# 05_LMS7002M_RF1.net
KiCad netlist of a schematic drawn in Altium Designer
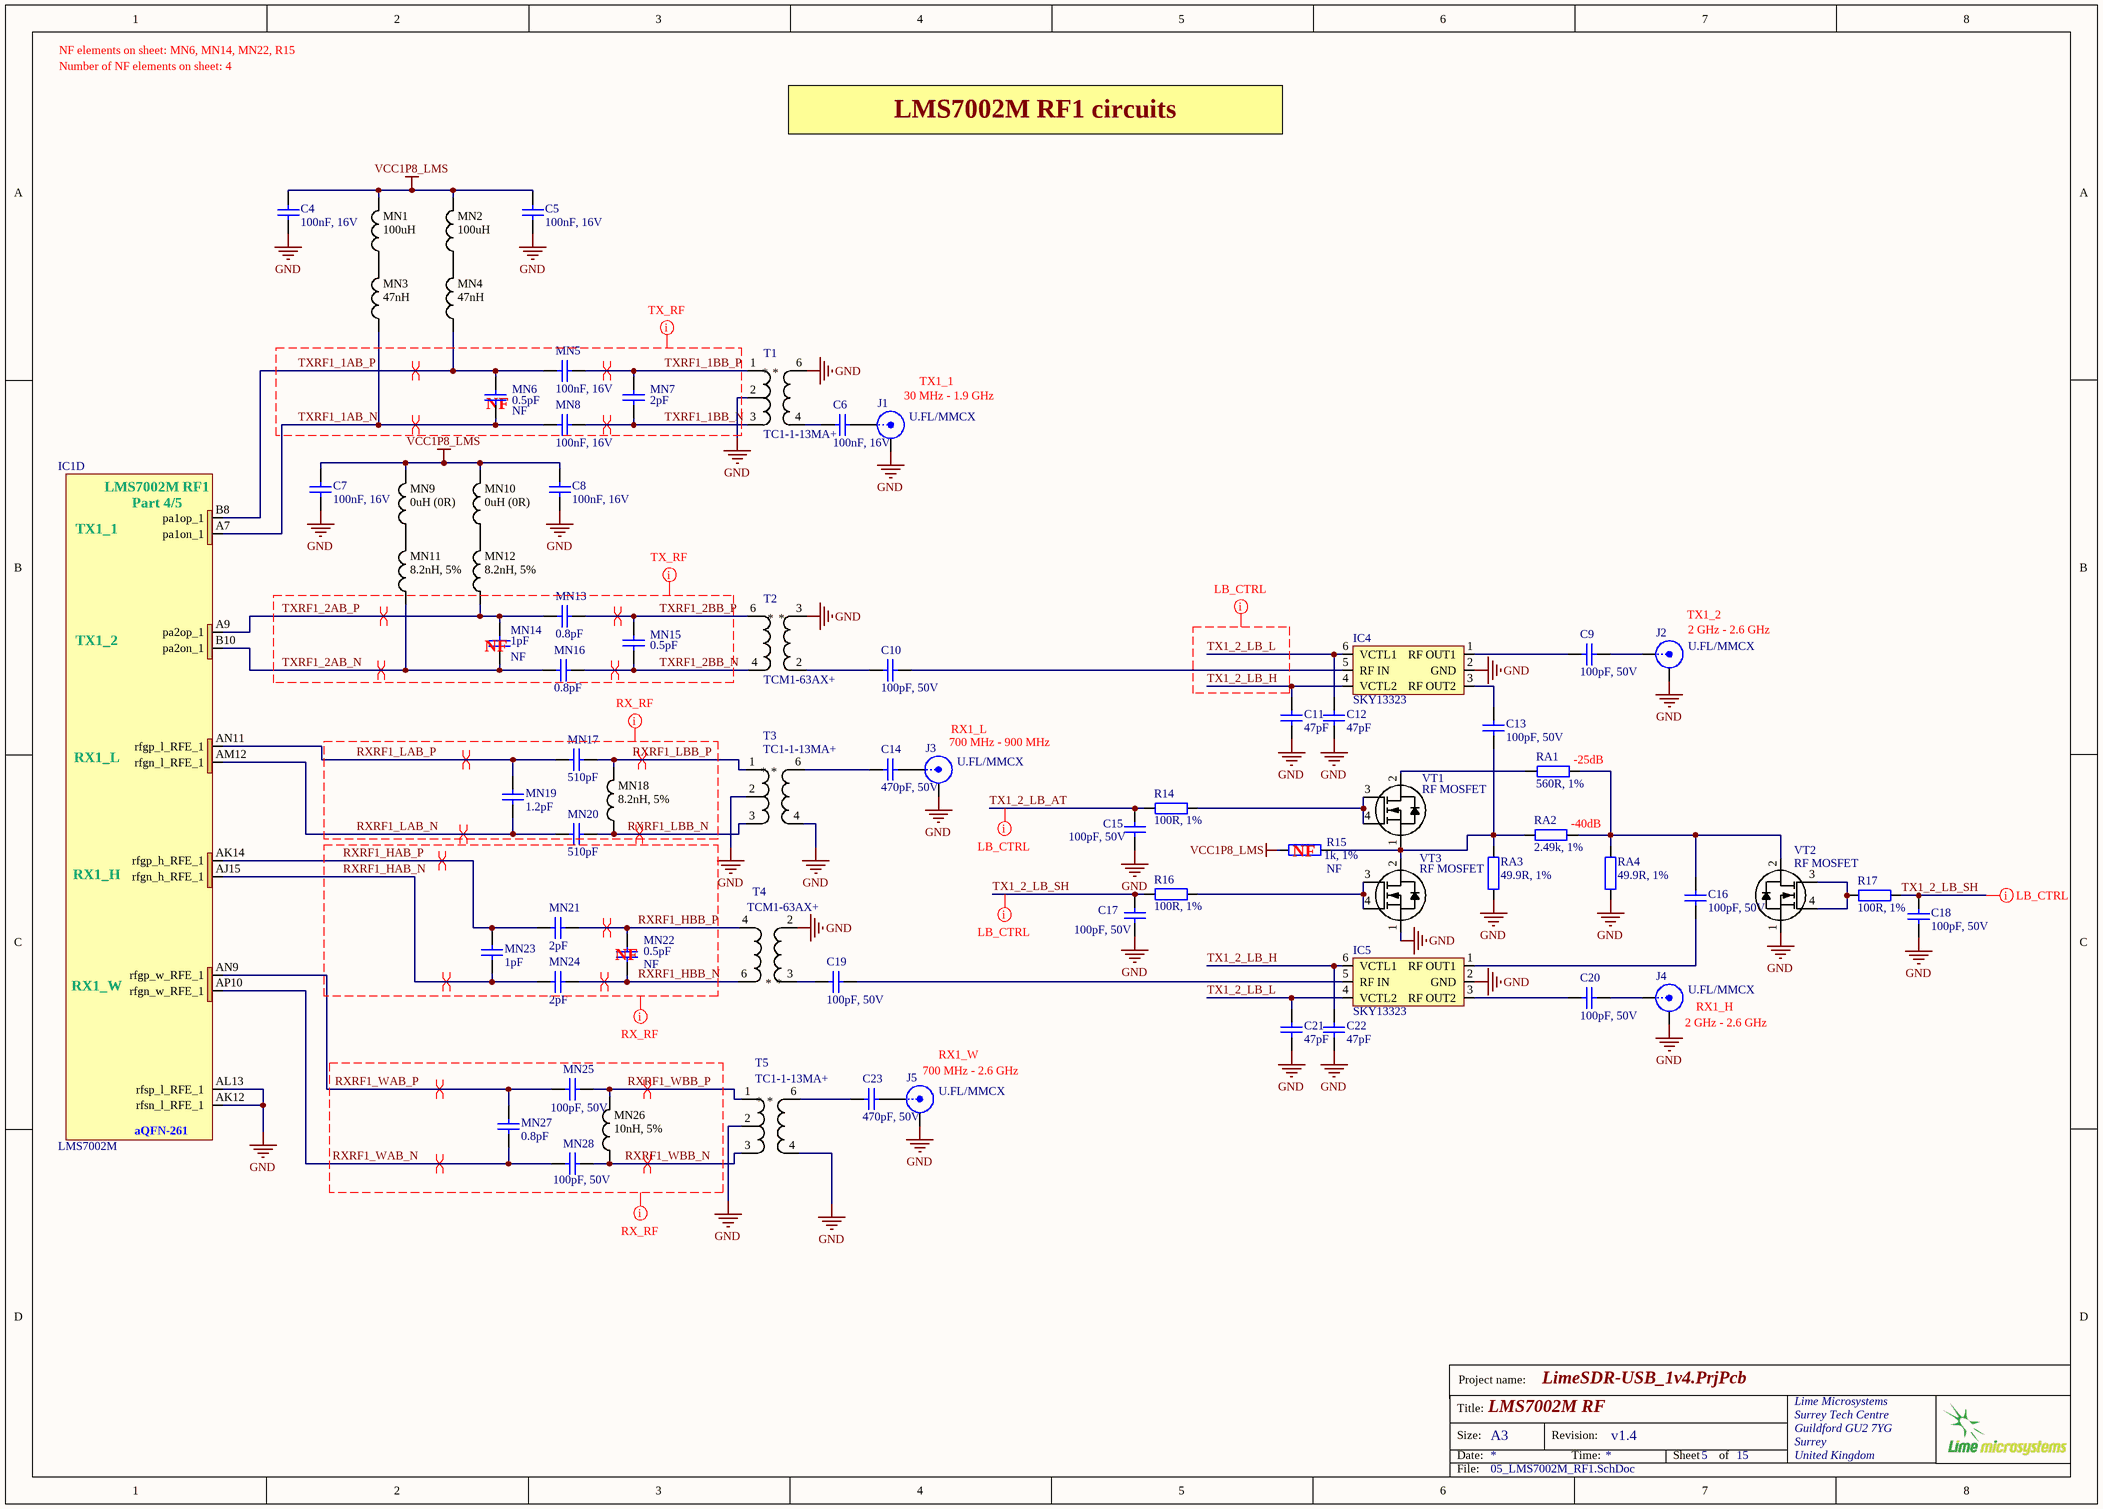
[diagram p0: 05_LMS7002M_RF1.SchDoc]

(export (version "E")
  (design (tool "Eeschema 10.0.6"))
  (components
    (comp (ref "C4")
      (value "100nF, 16V")
      (footprint "CAP0402")
      (fields
        (field (name "MANUFACTURER") "Murata Electronics")
        (field (name "TOLERANCE") "10 %")
        (field (name "MANUFACTURER PART NUMBER") "GRM155R71C104KA88D")
      )
      (libsource (lib "LimeMicroAltiumLib_schLib") (part "Cap_0402"))
    )
    (comp (ref "C5")
      (value "100nF, 16V")
      (footprint "CAP0402")
      (fields
        (field (name "MANUFACTURER") "Murata Electronics")
        (field (name "TOLERANCE") "10 %")
        (field (name "MANUFACTURER PART NUMBER") "GRM155R71C104KA88D")
      )
      (libsource (lib "LimeMicroAltiumLib_schLib") (part "Cap_0402"))
    )
    (comp (ref "C6")
      (value "100nF, 16V")
      (footprint "CAP0402")
      (fields
        (field (name "MANUFACTURER") "Murata Electronics")
        (field (name "TOLERANCE") "10 %")
        (field (name "MANUFACTURER PART NUMBER") "GRM155R71C104KA88D")
      )
      (libsource (lib "LimeMicroAltiumLib_schLib") (part "Cap_0402"))
    )
    (comp (ref "C7")
      (value "100nF, 16V")
      (footprint "CAP0402")
      (fields
        (field (name "MANUFACTURER") "Murata Electronics")
        (field (name "TOLERANCE") "10 %")
        (field (name "MANUFACTURER PART NUMBER") "GRM155R71C104KA88D")
      )
      (libsource (lib "LimeMicroAltiumLib_schLib") (part "Cap_0402"))
    )
    (comp (ref "C8")
      (value "100nF, 16V")
      (footprint "CAP0402")
      (fields
        (field (name "MANUFACTURER") "Murata Electronics")
        (field (name "TOLERANCE") "10 %")
        (field (name "MANUFACTURER PART NUMBER") "GRM155R71C104KA88D")
      )
      (libsource (lib "LimeMicroAltiumLib_schLib") (part "Cap_0402"))
    )
    (comp (ref "C9")
      (value "100pF, 50V")
      (footprint "CAP0402")
      (fields (field (name "TOLERANCE") "±5%") (field (name "MANUFACTURER") "Yageo"))
      (libsource (lib "LimeMicroAltiumLib_schLib") (part "Cap_0402"))
    )
    (comp (ref "C10")
      (value "100pF, 50V")
      (footprint "CAP0402")
      (fields (field (name "TOLERANCE") "±5%") (field (name "MANUFACTURER") "Yageo"))
      (libsource (lib "LimeMicroAltiumLib_schLib") (part "Cap_0402"))
    )
    (comp (ref "C11")
      (value "47pF")
      (footprint "CAP0402")
      (fields (field (name "TOLERANCE") "±1%") (field (name "MANUFACTURER") "TDK Corporation"))
      (libsource (lib "LimeMicroAltiumLib_schLib") (part "Cap_0402"))
    )
    (comp (ref "C12")
      (value "47pF")
      (footprint "CAP0402")
      (fields (field (name "TOLERANCE") "±1%") (field (name "MANUFACTURER") "TDK Corporation"))
      (libsource (lib "LimeMicroAltiumLib_schLib") (part "Cap_0402"))
    )
    (comp (ref "C13")
      (value "100pF, 50V")
      (footprint "CAP0402")
      (fields (field (name "TOLERANCE") "±5%") (field (name "MANUFACTURER") "Yageo"))
      (libsource (lib "LimeMicroAltiumLib_schLib") (part "Cap_0402"))
    )
    (comp (ref "C14")
      (value "470pF, 50V")
      (footprint "CAP0402")
      (fields
        (field (name "MANUFACTURER PART NUMBER") "C1005C0G1H471J050BA")
        (field (name "TOLERANCE") "±5%")
        (field (name "MANUFACTURER") "TDK Corporation")
      )
      (libsource (lib "LimeMicroAltiumLib_schLib") (part "Cap_0402"))
    )
    (comp (ref "C15")
      (value "100pF, 50V")
      (footprint "CAP0402")
      (fields (field (name "TOLERANCE") "±5%") (field (name "MANUFACTURER") "Yageo"))
      (libsource (lib "LimeMicroAltiumLib_schLib") (part "Cap_0402"))
    )
    (comp (ref "C16")
      (value "100pF, 50V")
      (footprint "CAP0402")
      (fields (field (name "TOLERANCE") "±5%") (field (name "MANUFACTURER") "Yageo"))
      (libsource (lib "LimeMicroAltiumLib_schLib") (part "Cap_0402"))
    )
    (comp (ref "C17")
      (value "100pF, 50V")
      (footprint "CAP0402")
      (fields (field (name "TOLERANCE") "±5%") (field (name "MANUFACTURER") "Yageo"))
      (libsource (lib "LimeMicroAltiumLib_schLib") (part "Cap_0402"))
    )
    (comp (ref "C18")
      (value "100pF, 50V")
      (footprint "CAP0402")
      (fields (field (name "TOLERANCE") "±5%") (field (name "MANUFACTURER") "Yageo"))
      (libsource (lib "LimeMicroAltiumLib_schLib") (part "Cap_0402"))
    )
    (comp (ref "C19")
      (value "100pF, 50V")
      (footprint "CAP0402")
      (fields (field (name "TOLERANCE") "±5%") (field (name "MANUFACTURER") "Yageo"))
      (libsource (lib "LimeMicroAltiumLib_schLib") (part "Cap_0402"))
    )
    (comp (ref "C20")
      (value "100pF, 50V")
      (footprint "CAP0402")
      (fields (field (name "TOLERANCE") "±5%") (field (name "MANUFACTURER") "Yageo"))
      (libsource (lib "LimeMicroAltiumLib_schLib") (part "Cap_0402"))
    )
    (comp (ref "C21")
      (value "47pF")
      (footprint "CAP0402")
      (fields (field (name "TOLERANCE") "±1%") (field (name "MANUFACTURER") "TDK Corporation"))
      (libsource (lib "LimeMicroAltiumLib_schLib") (part "Cap_0402"))
    )
    (comp (ref "C22")
      (value "47pF")
      (footprint "CAP0402")
      (fields (field (name "TOLERANCE") "±1%") (field (name "MANUFACTURER") "TDK Corporation"))
      (libsource (lib "LimeMicroAltiumLib_schLib") (part "Cap_0402"))
    )
    (comp (ref "C23")
      (value "470pF, 50V")
      (footprint "CAP0402")
      (fields
        (field (name "MANUFACTURER PART NUMBER") "C1005C0G1H471J050BA")
        (field (name "TOLERANCE") "±5%")
        (field (name "MANUFACTURER") "TDK Corporation")
      )
      (libsource (lib "LimeMicroAltiumLib_schLib") (part "Cap_0402"))
    )
    (comp (ref "IC1")
      (value "LMS7002M")
      (footprint "LMS7002M_v3")
      (fields (field (name "MANUFACTURER") "Lime Microsystems"))
      (libsource (lib "LimeMicroAltiumLib_schLib") (part "LMS7002M"))
    )
    (comp (ref "IC4")
      (value "SKY13323")
      (footprint "SKY13323-378LF")
      (description "SKY13323-378LF: 0.1-3.0 GHz GaAs SPDT Switch")
      (fields (field (name "MANUFACTURER") "Skyworks Solutions Inc."))
      (libsource (lib "LimeMicroAltiumLib_schLib") (part "SKY13323"))
    )
    (comp (ref "IC5")
      (value "SKY13323")
      (footprint "SKY13323-378LF")
      (description "SKY13323-378LF: 0.1-3.0 GHz GaAs SPDT Switch")
      (fields (field (name "MANUFACTURER") "Skyworks Solutions Inc."))
      (libsource (lib "LimeMicroAltiumLib_schLib") (part "SKY13323"))
    )
    (comp (ref "J1")
      (value "U.FL/MMCX")
      (footprint "MMCX_UFL_conn_u")
      (description "CONN UMC RCPT STR 50 OHM SMD")
      (fields (field (name "MANUFACTURER") "Molex, LLC"))
      (libsource (lib "LimeMicroAltiumLib_schLib") (part "RF_IF_connector"))
    )
    (comp (ref "J2")
      (value "U.FL/MMCX")
      (footprint "MMCX_UFL_conn_u")
      (description "CONN UMC RCPT STR 50 OHM SMD")
      (fields (field (name "MANUFACTURER") "Molex, LLC"))
      (libsource (lib "LimeMicroAltiumLib_schLib") (part "RF_IF_connector"))
    )
    (comp (ref "J3")
      (value "U.FL/MMCX")
      (footprint "MMCX_UFL_conn_u")
      (description "CONN UMC RCPT STR 50 OHM SMD")
      (fields (field (name "MANUFACTURER") "Molex, LLC"))
      (libsource (lib "LimeMicroAltiumLib_schLib") (part "RF_IF_connector"))
    )
    (comp (ref "J4")
      (value "U.FL/MMCX")
      (footprint "MMCX_UFL_conn_u")
      (description "CONN UMC RCPT STR 50 OHM SMD")
      (fields (field (name "MANUFACTURER") "Molex, LLC"))
      (libsource (lib "LimeMicroAltiumLib_schLib") (part "RF_IF_connector"))
    )
    (comp (ref "J5")
      (value "U.FL/MMCX")
      (footprint "MMCX_UFL_conn_u")
      (description "CONN UMC RCPT STR 50 OHM SMD")
      (fields (field (name "MANUFACTURER") "Molex, LLC"))
      (libsource (lib "LimeMicroAltiumLib_schLib") (part "RF_IF_connector"))
    )
    (comp (ref "MN1")
      (value "100uH")
      (footprint "RES0805")
      (fields
        (field (name "TOLERANCE") "±10%")
        (field (name "MANUFACTURER") "TDK Corporation")
        (field (name "MANUFACTURER PART NUMBER") "MLF2012C101KT000")
      )
      (libsource (lib "LimeMicroAltiumLib_schLib") (part "Inductor_0603"))
    )
    (comp (ref "MN2")
      (value "100uH")
      (footprint "RES0805")
      (fields
        (field (name "TOLERANCE") "±10%")
        (field (name "MANUFACTURER") "TDK Corporation")
        (field (name "MANUFACTURER PART NUMBER") "MLF2012C101KT000")
      )
      (libsource (lib "LimeMicroAltiumLib_schLib") (part "Inductor_0603"))
    )
    (comp (ref "MN3")
      (value "47nH")
      (footprint "RES0402")
      (fields
        (field (name "MANUFACTURER") "COILCRAFT")
        (field (name "MANUFACTURER PART NUMBER") "0402HP-47NXJLU")
      )
      (libsource (lib "LimeMicroAltiumLib_schLib") (part "Inductor_0603"))
    )
    (comp (ref "MN4")
      (value "47nH")
      (footprint "RES0402")
      (fields
        (field (name "MANUFACTURER") "COILCRAFT")
        (field (name "MANUFACTURER PART NUMBER") "0402HP-47NXJLU")
      )
      (libsource (lib "LimeMicroAltiumLib_schLib") (part "Inductor_0603"))
    )
    (comp (ref "MN5")
      (value "100nF, 16V")
      (footprint "CAP0402")
      (fields
        (field (name "MANUFACTURER") "Murata Electronics")
        (field (name "TOLERANCE") "10 %")
        (field (name "MANUFACTURER PART NUMBER") "GRM155R71C104KA88D")
      )
      (libsource (lib "LimeMicroAltiumLib_schLib") (part "Cap_0402"))
    )
    (comp (ref "MN6")
      (value "0.5pF")
      (footprint "CAP0402")
      (fields
        (field (name "ASSEMBLY INFO") "NF")
        (field (name "TOLERANCE") "±0.25pF")
        (field (name "MANUFACTURER") "Yageo")
      )
      (libsource (lib "LimeMicroAltiumLib_schLib") (part "Cap_0402"))
    )
    (comp (ref "MN7")
      (value "2pF")
      (footprint "CAP0402")
      (fields (field (name "MANUFACTURER PART NUMBER") "04025U2R0BAT2A") (field (name "MANUFACTURER") "AVX"))
      (libsource (lib "LimeMicroAltiumLib_schLib") (part "Cap_0402"))
    )
    (comp (ref "MN8")
      (value "100nF, 16V")
      (footprint "CAP0402")
      (fields
        (field (name "MANUFACTURER") "Murata Electronics")
        (field (name "TOLERANCE") "10 %")
        (field (name "MANUFACTURER PART NUMBER") "GRM155R71C104KA88D")
      )
      (libsource (lib "LimeMicroAltiumLib_schLib") (part "Cap_0402"))
    )
    (comp (ref "MN9")
      (value "0uH (0R)")
      (footprint "RES0805")
      (fields (field (name "MANUFACTURER") "BOURNS"))
      (libsource (lib "LimeMicroAltiumLib_schLib") (part "Inductor_0603"))
    )
    (comp (ref "MN10")
      (value "0uH (0R)")
      (footprint "RES0805")
      (fields (field (name "MANUFACTURER") "BOURNS"))
      (libsource (lib "LimeMicroAltiumLib_schLib") (part "Inductor_0603"))
    )
    (comp (ref "MN11")
      (value "8.2nH, 5%")
      (footprint "RES0402")
      (fields (field (name "MANUFACTURER") "COILCRAFT"))
      (libsource (lib "LimeMicroAltiumLib_schLib") (part "Inductor_0603"))
    )
    (comp (ref "MN12")
      (value "8.2nH, 5%")
      (footprint "RES0402")
      (fields (field (name "MANUFACTURER") "COILCRAFT"))
      (libsource (lib "LimeMicroAltiumLib_schLib") (part "Inductor_0603"))
    )
    (comp (ref "MN13")
      (value "0.8pF")
      (footprint "CAP0402")
      (fields
        (field (name "TOLERANCE") "±0.1pF")
        (field (name "MANUFACTURER") "Murata Electronics North America")
        (field (name "MANUFACTURER PART NUMBER") "GRM1555C1HR80BA01D")
      )
      (libsource (lib "LimeMicroAltiumLib_schLib") (part "Cap_0402"))
    )
    (comp (ref "MN14")
      (value "1pF")
      (footprint "CAP0402")
      (fields
        (field (name "ASSEMBLY INFO") "NF")
        (field (name "MANUFACTURER") "TDK Corporation")
        (field (name "TOLERANCE") "±0.1pF")
      )
      (libsource (lib "LimeMicroAltiumLib_schLib") (part "Cap_0402"))
    )
    (comp (ref "MN15")
      (value "0.5pF")
      (footprint "CAP0402")
      (fields (field (name "TOLERANCE") "±0.25pF") (field (name "MANUFACTURER") "Yageo"))
      (libsource (lib "LimeMicroAltiumLib_schLib") (part "Cap_0402"))
    )
    (comp (ref "MN16")
      (value "0.8pF")
      (footprint "CAP0402")
      (fields
        (field (name "TOLERANCE") "±0.1pF")
        (field (name "MANUFACTURER") "Murata Electronics North America")
        (field (name "MANUFACTURER PART NUMBER") "GRM1555C1HR80BA01D")
      )
      (libsource (lib "LimeMicroAltiumLib_schLib") (part "Cap_0402"))
    )
    (comp (ref "MN17")
      (value "510pF")
      (footprint "CAP0402")
      (fields
        (field (name "TOLERANCE") "±5%")
        (field (name "MANUFACTURER") "Murata Electronics North America")
        (field (name "MANUFACTURER PART NUMBER") "GRM1555C1H511JA01D")
      )
      (libsource (lib "LimeMicroAltiumLib_schLib") (part "Cap_0402"))
    )
    (comp (ref "MN18")
      (value "8.2nH, 5%")
      (footprint "RES0402")
      (fields (field (name "MANUFACTURER") "COILCRAFT"))
      (libsource (lib "LimeMicroAltiumLib_schLib") (part "Inductor_0603"))
    )
    (comp (ref "MN19")
      (value "1.2pF")
      (footprint "CAP0402")
      (fields
        (field (name "MANUFACTURER") "Murata Electronics North America")
        (field (name "MANUFACTURER PART NUMBER") "GRM1555C1H1R2CA01D")
        (field (name "TOLERANCE") "±0.25pF")
      )
      (libsource (lib "LimeMicroAltiumLib_schLib") (part "Cap_0402"))
    )
    (comp (ref "MN20")
      (value "510pF")
      (footprint "CAP0402")
      (fields
        (field (name "TOLERANCE") "±5%")
        (field (name "MANUFACTURER") "Murata Electronics North America")
        (field (name "MANUFACTURER PART NUMBER") "GRM1555C1H511JA01D")
      )
      (libsource (lib "LimeMicroAltiumLib_schLib") (part "Cap_0402"))
    )
    (comp (ref "MN21")
      (value "2pF")
      (footprint "CAP0402")
      (fields (field (name "MANUFACTURER PART NUMBER") "04025U2R0BAT2A") (field (name "MANUFACTURER") "AVX"))
      (libsource (lib "LimeMicroAltiumLib_schLib") (part "Cap_0402"))
    )
    (comp (ref "MN22")
      (value "0.5pF")
      (footprint "CAP0402")
      (fields
        (field (name "ASSEMBLY INFO") "NF")
        (field (name "TOLERANCE") "±0.25pF")
        (field (name "MANUFACTURER") "Yageo")
      )
      (libsource (lib "LimeMicroAltiumLib_schLib") (part "Cap_0402"))
    )
    (comp (ref "MN23")
      (value "1pF")
      (footprint "CAP0402")
      (fields (field (name "MANUFACTURER") "TDK Corporation") (field (name "TOLERANCE") "±0.1pF"))
      (libsource (lib "LimeMicroAltiumLib_schLib") (part "Cap_0402"))
    )
    (comp (ref "MN24")
      (value "2pF")
      (footprint "CAP0402")
      (fields (field (name "MANUFACTURER PART NUMBER") "04025U2R0BAT2A") (field (name "MANUFACTURER") "AVX"))
      (libsource (lib "LimeMicroAltiumLib_schLib") (part "Cap_0402"))
    )
    (comp (ref "MN25")
      (value "100pF, 50V")
      (footprint "CAP0402")
      (fields (field (name "TOLERANCE") "±5%") (field (name "MANUFACTURER") "Yageo"))
      (libsource (lib "LimeMicroAltiumLib_schLib") (part "Cap_0402"))
    )
    (comp (ref "MN26")
      (value "10nH, 5%")
      (footprint "RES0402")
      (fields (field (name "MANUFACTURER") "COILCRAFT"))
      (libsource (lib "LimeMicroAltiumLib_schLib") (part "Inductor_0603"))
    )
    (comp (ref "MN27")
      (value "0.8pF")
      (footprint "CAP0402")
      (fields
        (field (name "TOLERANCE") "±0.1pF")
        (field (name "MANUFACTURER") "Murata Electronics North America")
        (field (name "MANUFACTURER PART NUMBER") "GRM1555C1HR80BA01D")
      )
      (libsource (lib "LimeMicroAltiumLib_schLib") (part "Cap_0402"))
    )
    (comp (ref "MN28")
      (value "100pF, 50V")
      (footprint "CAP0402")
      (fields (field (name "TOLERANCE") "±5%") (field (name "MANUFACTURER") "Yageo"))
      (libsource (lib "LimeMicroAltiumLib_schLib") (part "Cap_0402"))
    )
    (comp (ref "R14")
      (value "100R, 1%")
      (footprint "RES0402")
      (fields (field (name "TOLERANCE") "±1%") (field (name "MANUFACTURER") "Stackpole Electronics Inc."))
      (libsource (lib "LimeFPGAboard_schLib") (part "Res_0402"))
    )
    (comp (ref "R15")
      (value "1k, 1%")
      (footprint "RES0402")
      (fields
        (field (name "ASSEMBLY INFO") "NF")
        (field (name "MANUFACTURER") "Stackpole Electronics Inc")
        (field (name "TOLERANCE") "±1%")
      )
      (libsource (lib "LimeMicroAltiumLib_schLib") (part "Res_0402"))
    )
    (comp (ref "R16")
      (value "100R, 1%")
      (footprint "RES0402")
      (fields (field (name "TOLERANCE") "±1%") (field (name "MANUFACTURER") "Stackpole Electronics Inc."))
      (libsource (lib "LimeFPGAboard_schLib") (part "Res_0402"))
    )
    (comp (ref "R17")
      (value "100R, 1%")
      (footprint "RES0402")
      (fields (field (name "TOLERANCE") "±1%") (field (name "MANUFACTURER") "Stackpole Electronics Inc."))
      (libsource (lib "LimeFPGAboard_schLib") (part "Res_0402"))
    )
    (comp (ref "RA1")
      (value "560R, 1%")
      (footprint "RES0402")
      (fields
        (field (name "MANUFACTURER PART NUMBER") "CRCW0402560RFKED")
        (field (name "TOLERANCE") "±1%")
        (field (name "MANUFACTURER") "Vishay Dale")
      )
      (libsource (lib "LimeMicroAltiumLib_schLib") (part "Res_0402"))
    )
    (comp (ref "RA2")
      (value "2.49k, 1%")
      (footprint "RES0402")
      (fields
        (field (name "TOLERANCE") "±1%")
        (field (name "MANUFACTURER PART NUMBER") "RC0402FR-072K49L")
        (field (name "MANUFACTURER") "Yageo")
      )
      (libsource (lib "LimeMicroAltiumLib_schLib") (part "Res_0402"))
    )
    (comp (ref "RA3")
      (value "49.9R, 1%")
      (footprint "RES0402")
      (fields
        (field (name "TOLERANCE") "±1%")
        (field (name "MANUFACTURER") "Samsung Electro-Mechanics America, Inc.")
        (field (name "MANUFACTURER PART NUMBER") "RC1005F49R9CS")
      )
      (libsource (lib "LimeMicroAltiumLib_schLib") (part "Res_0402"))
    )
    (comp (ref "RA4")
      (value "49.9R, 1%")
      (footprint "RES0402")
      (fields
        (field (name "TOLERANCE") "±1%")
        (field (name "MANUFACTURER") "Samsung Electro-Mechanics America, Inc.")
        (field (name "MANUFACTURER PART NUMBER") "RC1005F49R9CS")
      )
      (libsource (lib "LimeMicroAltiumLib_schLib") (part "Res_0402"))
    )
    (comp (ref "T1")
      (value "TC1-1-13MA+")
      (footprint "TC1-1-13MA+_v2")
      (fields (field (name "MANUFACTURER") "Mini-Circuits"))
      (libsource (lib "LimeMicroAltiumLib_schLib") (part "Balun"))
    )
    (comp (ref "T2")
      (value "TCM1-63AX+")
      (footprint "TCM1-63AX+_v2")
      (fields (field (name "MANUFACTURER") "Mini-circuits"))
      (libsource (lib "LimeMicroAltiumLib_schLib") (part "Balun_v2"))
    )
    (comp (ref "T3")
      (value "TC1-1-13MA+")
      (footprint "TC1-1-13MA+_v2")
      (fields (field (name "MANUFACTURER") "Mini-Circuits"))
      (libsource (lib "LimeMicroAltiumLib_schLib") (part "Balun"))
    )
    (comp (ref "T4")
      (value "TCM1-63AX+")
      (footprint "TCM1-63AX+_v2")
      (fields (field (name "MANUFACTURER") "Mini-circuits"))
      (libsource (lib "") (part "Balun_v2_1"))
    )
    (comp (ref "T5")
      (value "TC1-1-13MA+")
      (footprint "TC1-1-13MA+_v2")
      (fields (field (name "MANUFACTURER") "Mini-Circuits"))
      (libsource (lib "LimeMicroAltiumLib_schLib") (part "Balun"))
    )
    (comp (ref "VT1")
      (value "RF MOSFET")
      (footprint "BF1105R_SOT143R4")
      (fields (field (name "MANUFACTURER") "NXP Semiconductors"))
      (libsource (lib "LimeMicroAltiumLib_schLib") (part "BF1105R,215"))
    )
    (comp (ref "VT2")
      (value "RF MOSFET")
      (footprint "BF1105R_SOT143R4")
      (fields (field (name "MANUFACTURER") "NXP Semiconductors"))
      (libsource (lib "LimeMicroAltiumLib_schLib") (part "BF1105R,215"))
    )
    (comp (ref "VT3")
      (value "RF MOSFET")
      (footprint "BF1105R_SOT143R4")
      (fields (field (name "MANUFACTURER") "NXP Semiconductors"))
      (libsource (lib "LimeMicroAltiumLib_schLib") (part "BF1105R,215"))
    )
  )
  (nets
    (net (code "1") (name "/RXRF1_HAB_N") (class "Default")
      (node (ref "IC1") (pin "AJ15") (pinfunction "rfgn_h_RFE_1_AJ15") (pintype "passive"))
      (node (ref "MN23") (pin "1") (pinfunction "1_1") (pintype "passive"))
      (node (ref "MN24") (pin "2") (pinfunction "2_2") (pintype "passive"))
    )
    (net (code "2") (name "/RXRF1_HAB_P") (class "Default")
      (node (ref "IC1") (pin "AK14") (pinfunction "rfgp_h_RFE_1_AK14") (pintype "passive"))
      (node (ref "MN21") (pin "2") (pinfunction "2_2") (pintype "passive"))
      (node (ref "MN23") (pin "2") (pinfunction "2_2") (pintype "passive"))
    )
    (net (code "3") (name "/RXRF1_HBB_N") (class "Default")
      (node (ref "MN22") (pin "1") (pinfunction "1_1") (pintype "passive"))
      (node (ref "MN24") (pin "1") (pinfunction "1_1") (pintype "passive"))
      (node (ref "T4") (pin "6") (pinfunction "6_6") (pintype "passive"))
    )
    (net (code "4") (name "/RXRF1_HBB_P") (class "Default")
      (node (ref "MN21") (pin "1") (pinfunction "1_1") (pintype "passive"))
      (node (ref "MN22") (pin "2") (pinfunction "2_2") (pintype "passive"))
      (node (ref "T4") (pin "4") (pinfunction "4_4") (pintype "passive"))
    )
    (net (code "5") (name "/RXRF1_LAB_N") (class "Default")
      (node (ref "IC1") (pin "AM12") (pinfunction "rfgn_l_RFE_1_AM12") (pintype "passive"))
      (node (ref "MN19") (pin "1") (pinfunction "1_1") (pintype "passive"))
      (node (ref "MN20") (pin "2") (pinfunction "2_2") (pintype "passive"))
    )
    (net (code "6") (name "/RXRF1_LAB_P") (class "Default")
      (node (ref "IC1") (pin "AN11") (pinfunction "rfgp_l_RFE_1_AN11") (pintype "passive"))
      (node (ref "MN17") (pin "2") (pinfunction "2_2") (pintype "passive"))
      (node (ref "MN19") (pin "2") (pinfunction "2_2") (pintype "passive"))
    )
    (net (code "7") (name "/RXRF1_LBB_N") (class "Default")
      (node (ref "MN18") (pin "1") (pinfunction "1_1") (pintype "passive"))
      (node (ref "MN20") (pin "1") (pinfunction "1_1") (pintype "passive"))
      (node (ref "T3") (pin "3") (pinfunction "3_3") (pintype "passive"))
    )
    (net (code "8") (name "/RXRF1_LBB_P") (class "Default")
      (node (ref "MN17") (pin "1") (pinfunction "1_1") (pintype "passive"))
      (node (ref "MN18") (pin "2") (pinfunction "2_2") (pintype "passive"))
      (node (ref "T3") (pin "1") (pinfunction "1_1") (pintype "passive"))
    )
    (net (code "9") (name "/RXRF1_WAB_N") (class "Default")
      (node (ref "IC1") (pin "AP10") (pinfunction "rfgn_w_RFE_1_AP10") (pintype "passive"))
      (node (ref "MN27") (pin "2") (pinfunction "2_2") (pintype "passive"))
      (node (ref "MN28") (pin "2") (pinfunction "2_2") (pintype "passive"))
    )
    (net (code "10") (name "/RXRF1_WAB_P") (class "Default")
      (node (ref "IC1") (pin "AN9") (pinfunction "rfgp_w_RFE_1_AN9") (pintype "passive"))
      (node (ref "MN25") (pin "2") (pinfunction "2_2") (pintype "passive"))
      (node (ref "MN27") (pin "1") (pinfunction "1_1") (pintype "passive"))
    )
    (net (code "11") (name "/RXRF1_WBB_N") (class "Default")
      (node (ref "MN26") (pin "1") (pinfunction "1_1") (pintype "passive"))
      (node (ref "MN28") (pin "1") (pinfunction "1_1") (pintype "passive"))
      (node (ref "T5") (pin "3") (pinfunction "3_3") (pintype "passive"))
    )
    (net (code "12") (name "/RXRF1_WBB_P") (class "Default")
      (node (ref "MN25") (pin "1") (pinfunction "1_1") (pintype "passive"))
      (node (ref "MN26") (pin "2") (pinfunction "2_2") (pintype "passive"))
      (node (ref "T5") (pin "1") (pinfunction "1_1") (pintype "passive"))
    )
    (net (code "13") (name "/TX1_2_LB_AT") (class "Default")
      (node (ref "C15") (pin "1") (pinfunction "1_1") (pintype "passive"))
      (node (ref "R14") (pin "2") (pinfunction "2_2") (pintype "passive"))
    )
    (net (code "14") (name "/TX1_2_LB_H") (class "Default")
      (node (ref "C11") (pin "2") (pinfunction "2_2") (pintype "passive"))
      (node (ref "C22") (pin "2") (pinfunction "2_2") (pintype "passive"))
      (node (ref "IC4") (pin "4") (pinfunction "VCTL2_4") (pintype "input"))
      (node (ref "IC5") (pin "6") (pinfunction "VCTL1_6") (pintype "input"))
    )
    (net (code "15") (name "/TX1_2_LB_L") (class "Default")
      (node (ref "C12") (pin "2") (pinfunction "2_2") (pintype "passive"))
      (node (ref "C21") (pin "2") (pinfunction "2_2") (pintype "passive"))
      (node (ref "IC4") (pin "6") (pinfunction "VCTL1_6") (pintype "input"))
      (node (ref "IC5") (pin "4") (pinfunction "VCTL2_4") (pintype "input"))
    )
    (net (code "16") (name "/TX1_2_LB_SH") (class "Default")
      (node (ref "C17") (pin "1") (pinfunction "1_1") (pintype "passive"))
      (node (ref "C18") (pin "1") (pinfunction "1_1") (pintype "passive"))
      (node (ref "R16") (pin "2") (pinfunction "2_2") (pintype "passive"))
      (node (ref "R17") (pin "1") (pinfunction "1_1") (pintype "passive"))
    )
    (net (code "17") (name "/TXRF1_1AB_N") (class "Default")
      (node (ref "IC1") (pin "A7") (pinfunction "pa1on_1_A7") (pintype "passive"))
      (node (ref "MN3") (pin "1") (pinfunction "1_1") (pintype "passive"))
      (node (ref "MN6") (pin "1") (pinfunction "1_1") (pintype "passive"))
      (node (ref "MN8") (pin "1") (pinfunction "1_1") (pintype "passive"))
    )
    (net (code "18") (name "/TXRF1_1AB_P") (class "Default")
      (node (ref "IC1") (pin "B8") (pinfunction "pa1op_1_B8") (pintype "passive"))
      (node (ref "MN4") (pin "1") (pinfunction "1_1") (pintype "passive"))
      (node (ref "MN5") (pin "2") (pinfunction "2_2") (pintype "passive"))
      (node (ref "MN6") (pin "2") (pinfunction "2_2") (pintype "passive"))
    )
    (net (code "19") (name "/TXRF1_1BB_N") (class "Default")
      (node (ref "MN7") (pin "1") (pinfunction "1_1") (pintype "passive"))
      (node (ref "MN8") (pin "2") (pinfunction "2_2") (pintype "passive"))
      (node (ref "T1") (pin "3") (pinfunction "3_3") (pintype "passive"))
    )
    (net (code "20") (name "/TXRF1_1BB_P") (class "Default")
      (node (ref "MN5") (pin "1") (pinfunction "1_1") (pintype "passive"))
      (node (ref "MN7") (pin "2") (pinfunction "2_2") (pintype "passive"))
      (node (ref "T1") (pin "1") (pinfunction "1_1") (pintype "passive"))
    )
    (net (code "21") (name "/TXRF1_2AB_N") (class "Default")
      (node (ref "IC1") (pin "B10") (pinfunction "pa2on_1_B10") (pintype "passive"))
      (node (ref "MN11") (pin "1") (pinfunction "1_1") (pintype "passive"))
      (node (ref "MN14") (pin "2") (pinfunction "2_2") (pintype "passive"))
      (node (ref "MN16") (pin "2") (pinfunction "2_2") (pintype "passive"))
    )
    (net (code "22") (name "/TXRF1_2AB_P") (class "Default")
      (node (ref "IC1") (pin "A9") (pinfunction "pa2op_1_A9") (pintype "passive"))
      (node (ref "MN12") (pin "1") (pinfunction "1_1") (pintype "passive"))
      (node (ref "MN13") (pin "2") (pinfunction "2_2") (pintype "passive"))
      (node (ref "MN14") (pin "1") (pinfunction "1_1") (pintype "passive"))
    )
    (net (code "23") (name "/TXRF1_2BB_N") (class "Default")
      (node (ref "MN15") (pin "1") (pinfunction "1_1") (pintype "passive"))
      (node (ref "MN16") (pin "1") (pinfunction "1_1") (pintype "passive"))
      (node (ref "T2") (pin "4") (pinfunction "4_4") (pintype "passive"))
    )
    (net (code "24") (name "/TXRF1_2BB_P") (class "Default")
      (node (ref "MN13") (pin "1") (pinfunction "1_1") (pintype "passive"))
      (node (ref "MN15") (pin "2") (pinfunction "2_2") (pintype "passive"))
      (node (ref "T2") (pin "6") (pinfunction "6_6") (pintype "passive"))
    )
    (net (code "25") (name "GND") (class "Default")
      (node (ref "C11") (pin "1") (pinfunction "1_1") (pintype "passive"))
      (node (ref "C12") (pin "1") (pinfunction "1_1") (pintype "passive"))
      (node (ref "C15") (pin "2") (pinfunction "2_2") (pintype "passive"))
      (node (ref "C17") (pin "2") (pinfunction "2_2") (pintype "passive"))
      (node (ref "C18") (pin "2") (pinfunction "2_2") (pintype "passive"))
      (node (ref "C21") (pin "1") (pinfunction "1_1") (pintype "passive"))
      (node (ref "C22") (pin "1") (pinfunction "1_1") (pintype "passive"))
      (node (ref "C4") (pin "1") (pinfunction "1_1") (pintype "passive"))
      (node (ref "C5") (pin "1") (pinfunction "1_1") (pintype "passive"))
      (node (ref "C7") (pin "1") (pinfunction "1_1") (pintype "passive"))
      (node (ref "C8") (pin "1") (pinfunction "1_1") (pintype "passive"))
      (node (ref "IC1") (pin "AK12") (pinfunction "rfsn_l_RFE_1_AK12") (pintype "passive"))
      (node (ref "IC1") (pin "AL13") (pinfunction "rfsp_l_RFE_1_AL13") (pintype "passive"))
      (node (ref "IC4") (pin "2") (pinfunction "GND_2") (pintype "passive"))
      (node (ref "IC5") (pin "2") (pinfunction "GND_2") (pintype "passive"))
      (node (ref "J1") (pin "2") (pinfunction "Y_2") (pintype "passive"))
      (node (ref "J2") (pin "2") (pinfunction "Y_2") (pintype "passive"))
      (node (ref "J3") (pin "2") (pinfunction "Y_2") (pintype "passive"))
      (node (ref "J4") (pin "2") (pinfunction "Y_2") (pintype "passive"))
      (node (ref "J5") (pin "2") (pinfunction "Y_2") (pintype "passive"))
      (node (ref "RA3") (pin "1") (pinfunction "1_1") (pintype "passive"))
      (node (ref "RA4") (pin "1") (pinfunction "1_1") (pintype "passive"))
      (node (ref "T1") (pin "2") (pinfunction "2_2") (pintype "passive"))
      (node (ref "T1") (pin "6") (pinfunction "6_6") (pintype "passive"))
      (node (ref "T2") (pin "3") (pinfunction "3_3") (pintype "passive"))
      (node (ref "T3") (pin "2") (pinfunction "2_2") (pintype "passive"))
      (node (ref "T3") (pin "4") (pinfunction "4_4") (pintype "passive"))
      (node (ref "T4") (pin "2") (pinfunction "2_2") (pintype "passive"))
      (node (ref "T5") (pin "2") (pinfunction "2_2") (pintype "passive"))
      (node (ref "T5") (pin "4") (pinfunction "4_4") (pintype "passive"))
      (node (ref "VT2") (pin "1") (pinfunction "S_1") (pintype "passive"))
      (node (ref "VT3") (pin "1") (pinfunction "S_1") (pintype "passive"))
    )
    (net (code "26") (name "Net-(C6-Pad2)") (class "Default")
      (node (ref "C6") (pin "2") (pinfunction "2_2") (pintype "passive"))
      (node (ref "T1") (pin "4") (pinfunction "4_4") (pintype "passive"))
    )
    (net (code "27") (name "Net-(C10-Pad2)") (class "Default")
      (node (ref "C10") (pin "2") (pinfunction "2_2") (pintype "passive"))
      (node (ref "T2") (pin "2") (pinfunction "2_2") (pintype "passive"))
    )
    (net (code "28") (name "Net-(C14-Pad2)") (class "Default")
      (node (ref "C14") (pin "2") (pinfunction "2_2") (pintype "passive"))
      (node (ref "T3") (pin "6") (pinfunction "6_6") (pintype "passive"))
    )
    (net (code "29") (name "Net-(C19-Pad2)") (class "Default")
      (node (ref "C19") (pin "2") (pinfunction "2_2") (pintype "passive"))
      (node (ref "T4") (pin "3") (pinfunction "3_3") (pintype "passive"))
    )
    (net (code "30") (name "Net-(C23-Pad2)") (class "Default")
      (node (ref "C23") (pin "2") (pinfunction "2_2") (pintype "passive"))
      (node (ref "T5") (pin "6") (pinfunction "6_6") (pintype "passive"))
    )
    (net (code "31") (name "Net-(IC4-RF_IN)") (class "Default")
      (node (ref "C10") (pin "1") (pinfunction "1_1") (pintype "passive"))
      (node (ref "IC4") (pin "5") (pinfunction "RF_IN_5") (pintype "input"))
    )
    (net (code "32") (name "Net-(IC4-RF_OUT1)") (class "Default")
      (node (ref "C9") (pin "2") (pinfunction "2_2") (pintype "passive"))
      (node (ref "IC4") (pin "1") (pinfunction "RF_OUT1_1") (pintype "output"))
    )
    (net (code "33") (name "Net-(IC4-RF_OUT2)") (class "Default")
      (node (ref "C13") (pin "1") (pinfunction "1_1") (pintype "passive"))
      (node (ref "IC4") (pin "3") (pinfunction "RF_OUT2_3") (pintype "output"))
    )
    (net (code "34") (name "Net-(IC5-RF_IN)") (class "Default")
      (node (ref "C19") (pin "1") (pinfunction "1_1") (pintype "passive"))
      (node (ref "IC5") (pin "5") (pinfunction "RF_IN_5") (pintype "input"))
    )
    (net (code "35") (name "Net-(IC5-RF_OUT1)") (class "Default")
      (node (ref "C16") (pin "2") (pinfunction "2_2") (pintype "passive"))
      (node (ref "IC5") (pin "1") (pinfunction "RF_OUT1_1") (pintype "output"))
    )
    (net (code "36") (name "Net-(IC5-RF_OUT2)") (class "Default")
      (node (ref "C20") (pin "2") (pinfunction "2_2") (pintype "passive"))
      (node (ref "IC5") (pin "3") (pinfunction "RF_OUT2_3") (pintype "output"))
    )
    (net (code "37") (name "Net-(J1-X)") (class "Default")
      (node (ref "C6") (pin "1") (pinfunction "1_1") (pintype "passive"))
      (node (ref "J1") (pin "1") (pinfunction "X_1") (pintype "passive"))
    )
    (net (code "38") (name "Net-(J2-X)") (class "Default")
      (node (ref "C9") (pin "1") (pinfunction "1_1") (pintype "passive"))
      (node (ref "J2") (pin "1") (pinfunction "X_1") (pintype "passive"))
    )
    (net (code "39") (name "Net-(J3-X)") (class "Default")
      (node (ref "C14") (pin "1") (pinfunction "1_1") (pintype "passive"))
      (node (ref "J3") (pin "1") (pinfunction "X_1") (pintype "passive"))
    )
    (net (code "40") (name "Net-(J4-X)") (class "Default")
      (node (ref "C20") (pin "1") (pinfunction "1_1") (pintype "passive"))
      (node (ref "J4") (pin "1") (pinfunction "X_1") (pintype "passive"))
    )
    (net (code "41") (name "Net-(J5-X)") (class "Default")
      (node (ref "C23") (pin "1") (pinfunction "1_1") (pintype "passive"))
      (node (ref "J5") (pin "1") (pinfunction "X_1") (pintype "passive"))
    )
    (net (code "42") (name "Net-(MN1-Pad1)") (class "Default")
      (node (ref "MN1") (pin "1") (pinfunction "1_1") (pintype "passive"))
      (node (ref "MN3") (pin "2") (pinfunction "2_2") (pintype "passive"))
    )
    (net (code "43") (name "Net-(MN2-Pad1)") (class "Default")
      (node (ref "MN2") (pin "1") (pinfunction "1_1") (pintype "passive"))
      (node (ref "MN4") (pin "2") (pinfunction "2_2") (pintype "passive"))
    )
    (net (code "44") (name "Net-(MN10-Pad1)") (class "Default")
      (node (ref "MN10") (pin "1") (pinfunction "1_1") (pintype "passive"))
      (node (ref "MN12") (pin "2") (pinfunction "2_2") (pintype "passive"))
    )
    (net (code "45") (name "Net-(MN11-Pad2)") (class "Default")
      (node (ref "MN11") (pin "2") (pinfunction "2_2") (pintype "passive"))
      (node (ref "MN9") (pin "1") (pinfunction "1_1") (pintype "passive"))
    )
    (net (code "46") (name "Net-(VT1-D)") (class "Default")
      (node (ref "RA1") (pin "2") (pinfunction "2_2") (pintype "passive"))
      (node (ref "VT1") (pin "2") (pinfunction "D_2") (pintype "passive"))
    )
    (net (code "47") (name "Net-(VT1-G1)") (class "Default")
      (node (ref "R14") (pin "1") (pinfunction "1_1") (pintype "passive"))
      (node (ref "VT1") (pin "3") (pinfunction "G2_3") (pintype "passive"))
      (node (ref "VT1") (pin "4") (pinfunction "G1_4") (pintype "passive"))
    )
    (net (code "48") (name "Net-(VT1-S)") (class "Default")
      (node (ref "C13") (pin "2") (pinfunction "2_2") (pintype "passive"))
      (node (ref "R15") (pin "1") (pinfunction "1_1") (pintype "passive"))
      (node (ref "RA2") (pin "1") (pinfunction "1_1") (pintype "passive"))
      (node (ref "RA3") (pin "2") (pinfunction "2_2") (pintype "passive"))
      (node (ref "VT1") (pin "1") (pinfunction "S_1") (pintype "passive"))
      (node (ref "VT3") (pin "2") (pinfunction "D_2") (pintype "passive"))
    )
    (net (code "49") (name "Net-(VT2-D)") (class "Default")
      (node (ref "C16") (pin "1") (pinfunction "1_1") (pintype "passive"))
      (node (ref "RA1") (pin "1") (pinfunction "1_1") (pintype "passive"))
      (node (ref "RA2") (pin "2") (pinfunction "2_2") (pintype "passive"))
      (node (ref "RA4") (pin "2") (pinfunction "2_2") (pintype "passive"))
      (node (ref "VT2") (pin "2") (pinfunction "D_2") (pintype "passive"))
    )
    (net (code "50") (name "Net-(VT2-G1)") (class "Default")
      (node (ref "R17") (pin "2") (pinfunction "2_2") (pintype "passive"))
      (node (ref "VT2") (pin "3") (pinfunction "G2_3") (pintype "passive"))
      (node (ref "VT2") (pin "4") (pinfunction "G1_4") (pintype "passive"))
    )
    (net (code "51") (name "Net-(VT3-G1)") (class "Default")
      (node (ref "R16") (pin "1") (pinfunction "1_1") (pintype "passive"))
      (node (ref "VT3") (pin "3") (pinfunction "G2_3") (pintype "passive"))
      (node (ref "VT3") (pin "4") (pinfunction "G1_4") (pintype "passive"))
    )
    (net (code "52") (name "VCC1P8_LMS") (class "Default")
      (node (ref "C4") (pin "2") (pinfunction "2_2") (pintype "passive"))
      (node (ref "C5") (pin "2") (pinfunction "2_2") (pintype "passive"))
      (node (ref "C7") (pin "2") (pinfunction "2_2") (pintype "passive"))
      (node (ref "C8") (pin "2") (pinfunction "2_2") (pintype "passive"))
      (node (ref "MN1") (pin "2") (pinfunction "2_2") (pintype "passive"))
      (node (ref "MN10") (pin "2") (pinfunction "2_2") (pintype "passive"))
      (node (ref "MN2") (pin "2") (pinfunction "2_2") (pintype "passive"))
      (node (ref "MN9") (pin "2") (pinfunction "2_2") (pintype "passive"))
      (node (ref "R15") (pin "2") (pinfunction "2_2") (pintype "passive"))
    )
  )
)
